# detector328p-pu.net
KiCad netlist of a schematic drawn in EAGLE
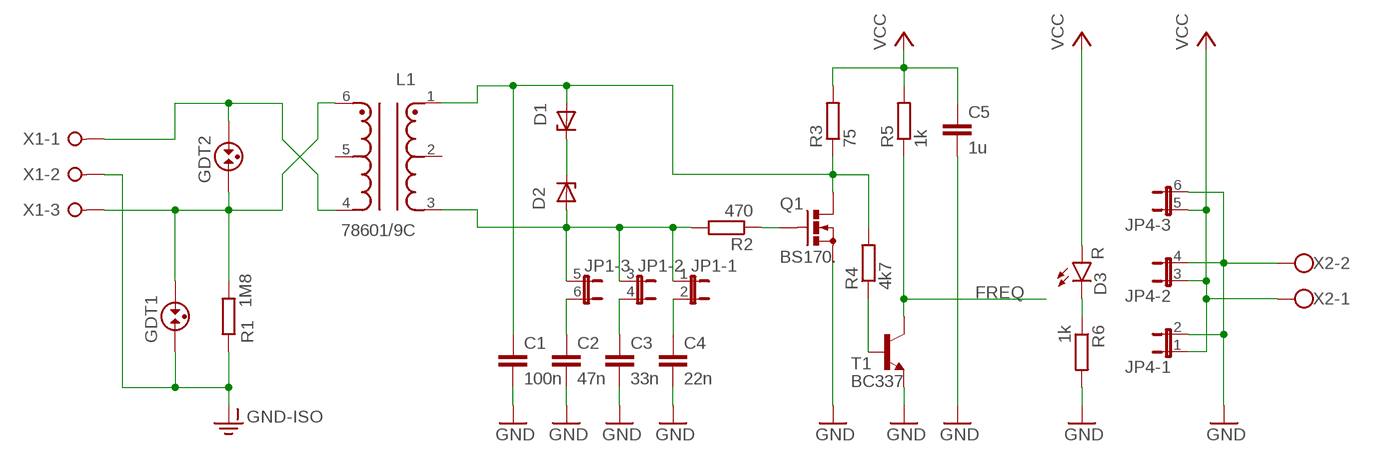
[diagram p0: schematic, sheet 1]
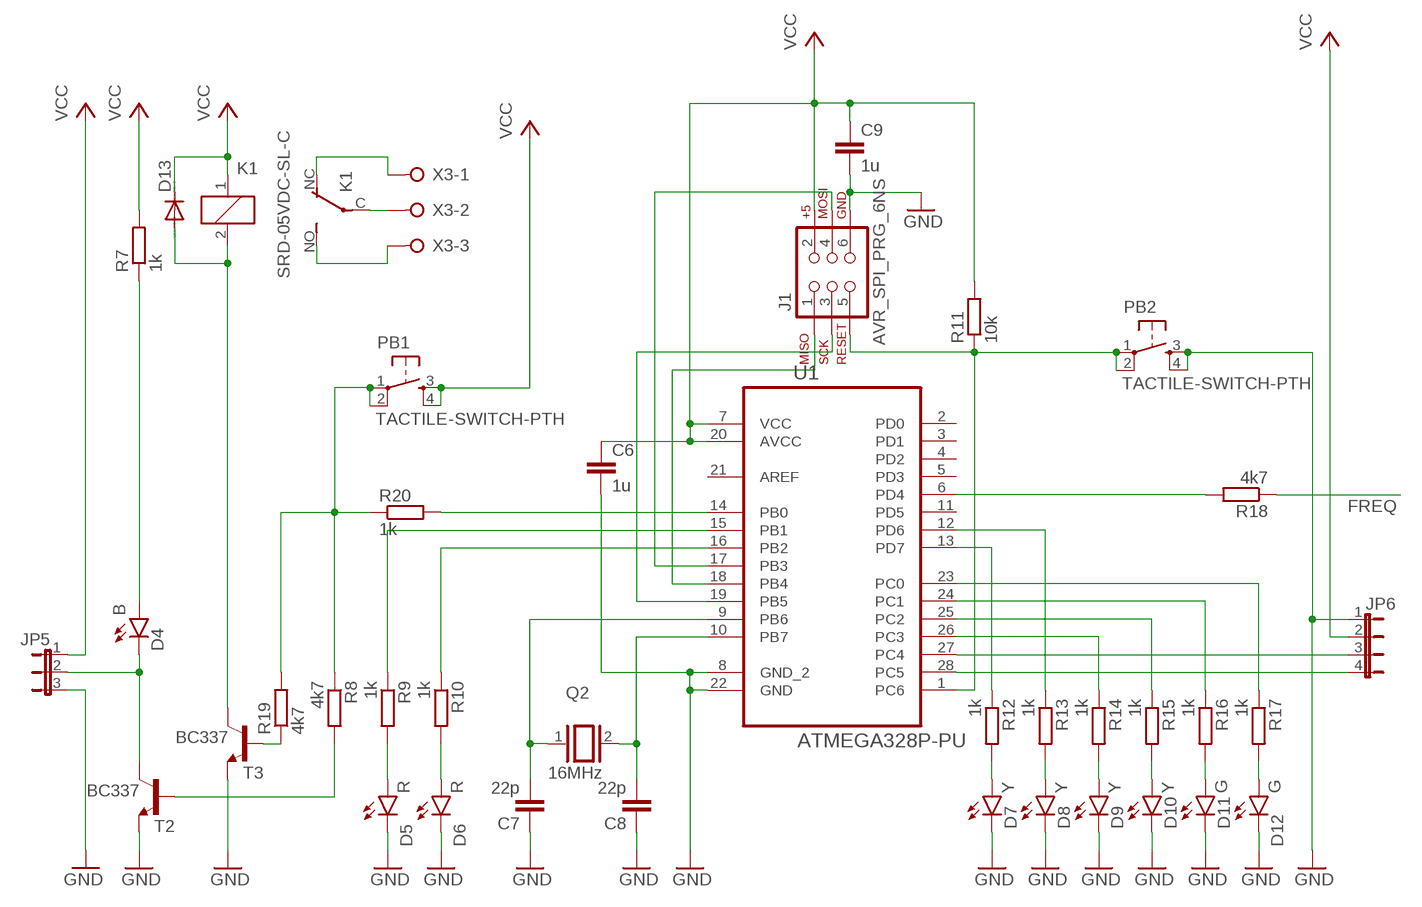
[diagram p1: schematic, sheet 2]

(export (version "E")
  (design (tool "Eeschema 10.0.6"))
  (components
    (comp (ref "C6")
      (value "1u")
      (footprint "eagle-import:C025-030X050")
      (libsource (lib "eagle-import") (part "C-EU025-030X050"))
    )
    (comp (ref "C7")
      (value "22p")
      (footprint "eagle-import:C025-025X050")
      (libsource (lib "eagle-import") (part "resistor_C-EU025-025X050"))
    )
    (comp (ref "C8")
      (value "22p")
      (footprint "eagle-import:C025-025X050")
      (libsource (lib "eagle-import") (part "resistor_C-EU025-025X050"))
    )
    (comp (ref "C9")
      (value "1u")
      (footprint "eagle-import:C025-030X050")
      (libsource (lib "eagle-import") (part "C-EU025-030X050"))
    )
    (comp (ref "D4")
      (value "B")
      (footprint "eagle-import:LED3MM")
      (libsource (lib "eagle-import") (part "LED3MM"))
    )
    (comp (ref "D5")
      (value "R")
      (footprint "eagle-import:LED3MM")
      (libsource (lib "eagle-import") (part "LED3MM"))
    )
    (comp (ref "D6")
      (value "R")
      (footprint "eagle-import:LED3MM")
      (libsource (lib "eagle-import") (part "LED3MM"))
    )
    (comp (ref "D7")
      (value "Y")
      (footprint "eagle-import:LED3MM")
      (libsource (lib "eagle-import") (part "LED3MM"))
    )
    (comp (ref "D8")
      (value "Y")
      (footprint "eagle-import:LED3MM")
      (libsource (lib "eagle-import") (part "LED3MM"))
    )
    (comp (ref "D9")
      (value "Y")
      (footprint "eagle-import:LED3MM")
      (libsource (lib "eagle-import") (part "LED3MM"))
    )
    (comp (ref "D10")
      (value "Y")
      (footprint "eagle-import:LED3MM")
      (libsource (lib "eagle-import") (part "LED3MM"))
    )
    (comp (ref "D11")
      (value "G")
      (footprint "eagle-import:LED3MM")
      (libsource (lib "eagle-import") (part "LED3MM"))
    )
    (comp (ref "D12")
      (value "G")
      (footprint "eagle-import:LED3MM")
      (libsource (lib "eagle-import") (part "LED3MM"))
    )
    (comp (ref "D13")
      (value "DIODE-D-5")
      (footprint "eagle-import:D-5")
      (libsource (lib "eagle-import") (part "DIODE-D-5"))
    )
    (comp (ref "J1")
      (value "AVR_SPI_PRG_6NS")
      (footprint "eagle-import:2X3-NS")
      (libsource (lib "eagle-import") (part "AVR_SPI_PRG_6NS"))
    )
    (comp (ref "JP5")
      (value "JP2E")
      (footprint "eagle-import:JP2")
      (libsource (lib "eagle-import") (part "JP2E"))
    )
    (comp (ref "JP6")
      (value "JP4E")
      (footprint "eagle-import:JP4")
      (libsource (lib "eagle-import") (part "JP4E"))
    )
    (comp (ref "K1")
      (value "SRD-05VDC-SL-C")
      (footprint "eagle-import:JS-M")
      (libsource (lib "eagle-import") (part "SRD--SL-C05VDC"))
    )
    (comp (ref "PB1")
      (value "TACTILE-SWITCH-PTH")
      (footprint "eagle-import:TAC-SWITCH-PTH")
      (libsource (lib "eagle-import") (part "TACTILE-SWITCH-PTH"))
    )
    (comp (ref "PB2")
      (value "TACTILE-SWITCH-PTH")
      (footprint "eagle-import:TAC-SWITCH-PTH")
      (libsource (lib "eagle-import") (part "TACTILE-SWITCH-PTH"))
    )
    (comp (ref "Q2")
      (value "16MHz")
      (footprint "eagle-import:QS")
      (libsource (lib "eagle-import") (part "XTAL/S"))
    )
    (comp (ref "R7")
      (value "1k")
      (footprint "eagle-import:0204_5")
      (libsource (lib "eagle-import") (part "R-EU_0204/5"))
    )
    (comp (ref "R8")
      (value "4k7")
      (footprint "eagle-import:0204_5")
      (libsource (lib "eagle-import") (part "R-EU_0204/5"))
    )
    (comp (ref "R9")
      (value "1k")
      (footprint "eagle-import:0204_5")
      (libsource (lib "eagle-import") (part "R-EU_0204/5"))
    )
    (comp (ref "R10")
      (value "1k")
      (footprint "eagle-import:0204_5")
      (libsource (lib "eagle-import") (part "R-EU_0204/5"))
    )
    (comp (ref "R11")
      (value "10k")
      (footprint "eagle-import:0204_5")
      (libsource (lib "eagle-import") (part "R-EU_0204/5"))
    )
    (comp (ref "R12")
      (value "1k")
      (footprint "eagle-import:0204_5")
      (libsource (lib "eagle-import") (part "R-EU_0204/5"))
    )
    (comp (ref "R13")
      (value "1k")
      (footprint "eagle-import:0204_5")
      (libsource (lib "eagle-import") (part "R-EU_0204/5"))
    )
    (comp (ref "R14")
      (value "1k")
      (footprint "eagle-import:0204_5")
      (libsource (lib "eagle-import") (part "R-EU_0204/5"))
    )
    (comp (ref "R15")
      (value "1k")
      (footprint "eagle-import:0204_5")
      (libsource (lib "eagle-import") (part "R-EU_0204/5"))
    )
    (comp (ref "R16")
      (value "1k")
      (footprint "eagle-import:0204_5")
      (libsource (lib "eagle-import") (part "R-EU_0204/5"))
    )
    (comp (ref "R17")
      (value "1k")
      (footprint "eagle-import:0204_5")
      (libsource (lib "eagle-import") (part "R-EU_0204/5"))
    )
    (comp (ref "R18")
      (value "4k7")
      (footprint "eagle-import:0204_5")
      (libsource (lib "eagle-import") (part "R-EU_0204/5"))
    )
    (comp (ref "R19")
      (value "4k7")
      (footprint "eagle-import:0204_5")
      (libsource (lib "eagle-import") (part "R-EU_0204/5"))
    )
    (comp (ref "R20")
      (value "1k")
      (footprint "eagle-import:0204_5")
      (libsource (lib "eagle-import") (part "R-EU_0204/5"))
    )
    (comp (ref "T2")
      (value "BC337")
      (footprint "eagle-import:TO92-CBE")
      (libsource (lib "eagle-import") (part "-NPN-TO92-CBEBC337"))
    )
    (comp (ref "T3")
      (value "BC337")
      (footprint "eagle-import:TO92-CBE")
      (libsource (lib "eagle-import") (part "-NPN-TO92-CBEBC337"))
    )
    (comp (ref "U1")
      (value "ATMEGA328P-PU")
      (footprint "eagle-import:DIP254P762X457-28")
      (libsource (lib "eagle-import") (part "ATMEGA328P-PU"))
    )
    (comp (ref "X3")
      (value "W237-03P")
      (footprint "eagle-import:W237-133")
      (libsource (lib "eagle-import") (part "W237-03P"))
    )
    (comp (ref "C1")
      (value "100n")
      (footprint "eagle-import:C025-025X050")
      (libsource (lib "eagle-import") (part "resistor_C-EU025-025X050"))
    )
    (comp (ref "C2")
      (value "47n")
      (footprint "eagle-import:C025-025X050")
      (libsource (lib "eagle-import") (part "resistor_C-EU025-025X050"))
    )
    (comp (ref "C3")
      (value "33n")
      (footprint "eagle-import:C025-025X050")
      (libsource (lib "eagle-import") (part "resistor_C-EU025-025X050"))
    )
    (comp (ref "C4")
      (value "22n")
      (footprint "eagle-import:C025-025X050")
      (libsource (lib "eagle-import") (part "resistor_C-EU025-025X050"))
    )
    (comp (ref "C5")
      (value "1u")
      (footprint "eagle-import:C025-030X050")
      (libsource (lib "eagle-import") (part "C-EU025-030X050"))
    )
    (comp (ref "D1")
      (value "24V")
      (footprint "eagle-import:ZDIO-5")
      (libsource (lib "eagle-import") (part "ZENER-DIODEZD-5"))
    )
    (comp (ref "D2")
      (value "24V")
      (footprint "eagle-import:ZDIO-5")
      (libsource (lib "eagle-import") (part "ZENER-DIODEZD-5"))
    )
    (comp (ref "D3")
      (value "R")
      (footprint "eagle-import:LED3MM")
      (libsource (lib "eagle-import") (part "LED3MM"))
    )
    (comp (ref "GDT1")
      (value "GDT-CG5350L")
      (footprint "eagle-import:CG5350L")
      (libsource (lib "eagle-import") (part "GDT-CG5350L"))
    )
    (comp (ref "GDT2")
      (value "GDT-CG5350L")
      (footprint "eagle-import:CG5350L")
      (libsource (lib "eagle-import") (part "GDT-CG5350L"))
    )
    (comp (ref "JP1")
      (value "JP3QE")
      (footprint "eagle-import:JP3Q")
      (libsource (lib "eagle-import") (part "JP3QE"))
    )
    (comp (ref "JP4")
      (value "JP3QE")
      (footprint "eagle-import:JP3Q")
      (libsource (lib "eagle-import") (part "JP3QE"))
    )
    (comp (ref "L1")
      (value "78601/9C")
      (footprint "eagle-import:78601_9C")
      (libsource (lib "eagle-import") (part "78601/9C"))
    )
    (comp (ref "Q1")
      (value "BS170.")
      (footprint "eagle-import:TO92-DGS")
      (libsource (lib "eagle-import") (part "BS170."))
    )
    (comp (ref "R1")
      (value "1M8")
      (footprint "eagle-import:0204_5")
      (libsource (lib "eagle-import") (part "R-EU_0204/5"))
    )
    (comp (ref "R2")
      (value "470")
      (footprint "eagle-import:0204_5")
      (libsource (lib "eagle-import") (part "R-EU_0204/5"))
    )
    (comp (ref "R3")
      (value "75")
      (footprint "eagle-import:0204_7")
      (libsource (lib "eagle-import") (part "R-EU_0204/7"))
    )
    (comp (ref "R4")
      (value "4k7")
      (footprint "eagle-import:0204_5")
      (libsource (lib "eagle-import") (part "R-EU_0204/5"))
    )
    (comp (ref "R5")
      (value "1k")
      (footprint "eagle-import:0204_5")
      (libsource (lib "eagle-import") (part "R-EU_0204/5"))
    )
    (comp (ref "R6")
      (value "1k")
      (footprint "eagle-import:0204_5")
      (libsource (lib "eagle-import") (part "R-EU_0204/5"))
    )
    (comp (ref "T1")
      (value "BC337")
      (footprint "eagle-import:TO92-CBE")
      (libsource (lib "eagle-import") (part "-NPN-TO92-CBEBC337"))
    )
    (comp (ref "X1")
      (value "W237-03P")
      (footprint "eagle-import:W237-133")
      (libsource (lib "eagle-import") (part "W237-03P"))
    )
    (comp (ref "X2")
      (value "W237-102")
      (footprint "eagle-import:W237-102")
      (fields (field (name "MPN") "237-102"))
      (libsource (lib "eagle-import") (part "W237-102"))
    )
  )
  (nets
    (net (code "1") (name "FREQ") (class "Default")
      (node (ref "R18") (pin "1") (pinfunction "1_1") (pintype "passive"))
      (node (ref "R5") (pin "1") (pinfunction "1_1") (pintype "passive"))
      (node (ref "T1") (pin "C") (pinfunction "C_C") (pintype "passive"))
    )
    (net (code "2") (name "GND") (class "Default")
      (node (ref "C1") (pin "2") (pinfunction "2_2") (pintype "passive"))
      (node (ref "C2") (pin "2") (pinfunction "2_2") (pintype "passive"))
      (node (ref "C3") (pin "2") (pinfunction "2_2") (pintype "passive"))
      (node (ref "C4") (pin "2") (pinfunction "2_2") (pintype "passive"))
      (node (ref "C5") (pin "2") (pinfunction "2_2") (pintype "passive"))
      (node (ref "C6") (pin "2") (pinfunction "2_2") (pintype "passive"))
      (node (ref "C7") (pin "1") (pinfunction "1_1") (pintype "passive"))
      (node (ref "C8") (pin "1") (pinfunction "1_1") (pintype "passive"))
      (node (ref "C9") (pin "2") (pinfunction "2_2") (pintype "passive"))
      (node (ref "D10") (pin "K") (pinfunction "C_K") (pintype "passive"))
      (node (ref "D11") (pin "K") (pinfunction "C_K") (pintype "passive"))
      (node (ref "D12") (pin "K") (pinfunction "C_K") (pintype "passive"))
      (node (ref "D5") (pin "K") (pinfunction "C_K") (pintype "passive"))
      (node (ref "D6") (pin "K") (pinfunction "C_K") (pintype "passive"))
      (node (ref "D7") (pin "K") (pinfunction "C_K") (pintype "passive"))
      (node (ref "D8") (pin "K") (pinfunction "C_K") (pintype "passive"))
      (node (ref "D9") (pin "K") (pinfunction "C_K") (pintype "passive"))
      (node (ref "J1") (pin "6") (pinfunction "6_6") (pintype "passive"))
      (node (ref "JP4") (pin "2") (pinfunction "2_2") (pintype "passive"))
      (node (ref "JP4") (pin "4") (pinfunction "2_4") (pintype "passive"))
      (node (ref "JP4") (pin "6") (pinfunction "2_6") (pintype "passive"))
      (node (ref "JP5") (pin "3") (pinfunction "3_3") (pintype "passive"))
      (node (ref "JP6") (pin "1") (pinfunction "1_1") (pintype "passive"))
      (node (ref "PB2") (pin "3") (pinfunction "3_3") (pintype "passive"))
      (node (ref "PB2") (pin "4") (pinfunction "4_4") (pintype "passive"))
      (node (ref "Q1") (pin "S") (pinfunction "S_S") (pintype "passive"))
      (node (ref "R6") (pin "2") (pinfunction "2_2") (pintype "passive"))
      (node (ref "T1") (pin "E") (pinfunction "E_E") (pintype "passive"))
      (node (ref "T2") (pin "E") (pinfunction "E_E") (pintype "passive"))
      (node (ref "T3") (pin "E") (pinfunction "E_E") (pintype "passive"))
      (node (ref "U1") (pin "22") (pinfunction "GND_22") (pintype "passive"))
      (node (ref "U1") (pin "8") (pinfunction "GND_2_8") (pintype "passive"))
      (node (ref "X2") (pin "2") (pinfunction "KL_2") (pintype "passive"))
    )
    (net (code "3") (name "GND-ISO") (class "Default")
      (node (ref "GDT1") (pin "1") (pinfunction "1_1") (pintype "passive"))
      (node (ref "R1") (pin "1") (pinfunction "1_1") (pintype "passive"))
      (node (ref "X1") (pin "2") (pinfunction "KL_2") (pintype "passive"))
    )
    (net (code "4") (name "Net-(C1-Pad1)") (class "Default")
      (node (ref "C1") (pin "1") (pinfunction "1_1") (pintype "passive"))
      (node (ref "D1") (pin "A") (pinfunction "A_A") (pintype "passive"))
      (node (ref "L1") (pin "1") (pinfunction "1_1") (pintype "passive"))
      (node (ref "Q1") (pin "D") (pinfunction "D_D") (pintype "passive"))
      (node (ref "R3") (pin "1") (pinfunction "1_1") (pintype "passive"))
      (node (ref "R4") (pin "2") (pinfunction "2_2") (pintype "passive"))
    )
    (net (code "5") (name "Net-(C4-Pad1)") (class "Default")
      (node (ref "C4") (pin "1") (pinfunction "1_1") (pintype "passive"))
      (node (ref "JP1") (pin "2") (pinfunction "2_2") (pintype "passive"))
    )
    (net (code "6") (name "Net-(D1-PadC)") (class "Default")
      (node (ref "D1") (pin "C") (pinfunction "C_C") (pintype "passive"))
      (node (ref "D2") (pin "C") (pinfunction "C_C") (pintype "passive"))
    )
    (net (code "7") (name "Net-(D3-C)") (class "Default")
      (node (ref "D3") (pin "K") (pinfunction "C_K") (pintype "passive"))
      (node (ref "R6") (pin "1") (pinfunction "1_1") (pintype "passive"))
    )
    (net (code "8") (name "Net-(D4-C)") (class "Default")
      (node (ref "D4") (pin "K") (pinfunction "C_K") (pintype "passive"))
      (node (ref "JP5") (pin "2") (pinfunction "2_2") (pintype "passive"))
      (node (ref "T2") (pin "C") (pinfunction "C_C") (pintype "passive"))
    )
    (net (code "9") (name "Net-(D4-PadA)") (class "Default")
      (node (ref "D4") (pin "A") (pinfunction "A_A") (pintype "passive"))
      (node (ref "R7") (pin "1") (pinfunction "1_1") (pintype "passive"))
    )
    (net (code "10") (name "Net-(D5-PadA)") (class "Default")
      (node (ref "D5") (pin "A") (pinfunction "A_A") (pintype "passive"))
      (node (ref "R9") (pin "2") (pinfunction "2_2") (pintype "passive"))
    )
    (net (code "11") (name "Net-(D6-PadA)") (class "Default")
      (node (ref "D6") (pin "A") (pinfunction "A_A") (pintype "passive"))
      (node (ref "R10") (pin "2") (pinfunction "2_2") (pintype "passive"))
    )
    (net (code "12") (name "Net-(D7-PadA)") (class "Default")
      (node (ref "D7") (pin "A") (pinfunction "A_A") (pintype "passive"))
      (node (ref "R12") (pin "2") (pinfunction "2_2") (pintype "passive"))
    )
    (net (code "13") (name "Net-(D8-PadA)") (class "Default")
      (node (ref "D8") (pin "A") (pinfunction "A_A") (pintype "passive"))
      (node (ref "R13") (pin "2") (pinfunction "2_2") (pintype "passive"))
    )
    (net (code "14") (name "Net-(D9-PadA)") (class "Default")
      (node (ref "D9") (pin "A") (pinfunction "A_A") (pintype "passive"))
      (node (ref "R14") (pin "2") (pinfunction "2_2") (pintype "passive"))
    )
    (net (code "15") (name "Net-(D10-PadA)") (class "Default")
      (node (ref "D10") (pin "A") (pinfunction "A_A") (pintype "passive"))
      (node (ref "R15") (pin "2") (pinfunction "2_2") (pintype "passive"))
    )
    (net (code "16") (name "Net-(D11-PadA)") (class "Default")
      (node (ref "D11") (pin "A") (pinfunction "A_A") (pintype "passive"))
      (node (ref "R16") (pin "2") (pinfunction "2_2") (pintype "passive"))
    )
    (net (code "17") (name "Net-(D12-PadA)") (class "Default")
      (node (ref "D12") (pin "A") (pinfunction "A_A") (pintype "passive"))
      (node (ref "R17") (pin "2") (pinfunction "2_2") (pintype "passive"))
    )
    (net (code "18") (name "Net-(D13-PadA)") (class "Default")
      (node (ref "D13") (pin "A") (pinfunction "A_A") (pintype "passive"))
      (node (ref "K1") (pin "2") (pinfunction "2_2") (pintype "passive"))
      (node (ref "T3") (pin "C") (pinfunction "C_C") (pintype "passive"))
    )
    (net (code "19") (name "Net-(JP1B-1)") (class "Default")
      (node (ref "D2") (pin "A") (pinfunction "A_A") (pintype "passive"))
      (node (ref "JP1") (pin "1") (pinfunction "1_1") (pintype "passive"))
      (node (ref "JP1") (pin "3") (pinfunction "1_3") (pintype "passive"))
      (node (ref "JP1") (pin "5") (pinfunction "1_5") (pintype "passive"))
      (node (ref "L1") (pin "3") (pinfunction "3_3") (pintype "passive"))
      (node (ref "R2") (pin "2") (pinfunction "2_2") (pintype "passive"))
    )
    (net (code "20") (name "Net-(JP1B-2)") (class "Default")
      (node (ref "C3") (pin "1") (pinfunction "1_1") (pintype "passive"))
      (node (ref "JP1") (pin "4") (pinfunction "2_4") (pintype "passive"))
    )
    (net (code "21") (name "Net-(JP1C-2)") (class "Default")
      (node (ref "C2") (pin "1") (pinfunction "1_1") (pintype "passive"))
      (node (ref "JP1") (pin "6") (pinfunction "2_6") (pintype "passive"))
    )
    (net (code "22") (name "Net-(K1B-O)") (class "Default")
      (node (ref "K1") (pin "NC") (pinfunction "O_NC") (pintype "passive"))
      (node (ref "X3") (pin "1") (pinfunction "KL_1") (pintype "passive"))
    )
    (net (code "23") (name "Net-(K1B-P)") (class "Default")
      (node (ref "K1") (pin "C") (pinfunction "P_C") (pintype "passive"))
      (node (ref "X3") (pin "2") (pinfunction "KL_2") (pintype "passive"))
    )
    (net (code "24") (name "Net-(K1B-S)") (class "Default")
      (node (ref "K1") (pin "NO") (pinfunction "S_NO") (pintype "passive"))
      (node (ref "X3") (pin "3") (pinfunction "KL_3") (pintype "passive"))
    )
    (net (code "25") (name "Net-(PB1-Pad1)") (class "Default")
      (node (ref "PB1") (pin "1") (pinfunction "1_1") (pintype "passive"))
      (node (ref "PB1") (pin "2") (pinfunction "2_2") (pintype "passive"))
      (node (ref "R19") (pin "2") (pinfunction "2_2") (pintype "passive"))
      (node (ref "R20") (pin "1") (pinfunction "1_1") (pintype "passive"))
      (node (ref "R8") (pin "1") (pinfunction "1_1") (pintype "passive"))
    )
    (net (code "26") (name "Net-(Q1-PadG)") (class "Default")
      (node (ref "Q1") (pin "G") (pinfunction "G_G") (pintype "passive"))
      (node (ref "R2") (pin "1") (pinfunction "1_1") (pintype "passive"))
    )
    (net (code "27") (name "Net-(R4-Pad1)") (class "Default")
      (node (ref "R4") (pin "1") (pinfunction "1_1") (pintype "passive"))
      (node (ref "T1") (pin "B") (pinfunction "B_B") (pintype "passive"))
    )
    (net (code "28") (name "Net-(R8-Pad2)") (class "Default")
      (node (ref "R8") (pin "2") (pinfunction "2_2") (pintype "passive"))
      (node (ref "T2") (pin "B") (pinfunction "B_B") (pintype "passive"))
    )
    (net (code "29") (name "Net-(R19-Pad1)") (class "Default")
      (node (ref "R19") (pin "1") (pinfunction "1_1") (pintype "passive"))
      (node (ref "T3") (pin "B") (pinfunction "B_B") (pintype "passive"))
    )
    (net (code "30") (name "Net-(U1-PB0)") (class "Default")
      (node (ref "R20") (pin "2") (pinfunction "2_2") (pintype "passive"))
      (node (ref "U1") (pin "14") (pinfunction "PB0_14") (pintype "bidirectional"))
    )
    (net (code "31") (name "Net-(U1-PB1)") (class "Default")
      (node (ref "R9") (pin "1") (pinfunction "1_1") (pintype "passive"))
      (node (ref "U1") (pin "15") (pinfunction "PB1_15") (pintype "bidirectional"))
    )
    (net (code "32") (name "Net-(U1-PB2)") (class "Default")
      (node (ref "R10") (pin "1") (pinfunction "1_1") (pintype "passive"))
      (node (ref "U1") (pin "16") (pinfunction "PB2_16") (pintype "bidirectional"))
    )
    (net (code "33") (name "Net-(U1-PB3)") (class "Default")
      (node (ref "J1") (pin "4") (pinfunction "4_4") (pintype "passive"))
      (node (ref "U1") (pin "17") (pinfunction "PB3_17") (pintype "bidirectional"))
    )
    (net (code "34") (name "Net-(U1-PB4)") (class "Default")
      (node (ref "J1") (pin "1") (pinfunction "1_1") (pintype "passive"))
      (node (ref "U1") (pin "18") (pinfunction "PB4_18") (pintype "bidirectional"))
    )
    (net (code "35") (name "Net-(U1-PB5)") (class "Default")
      (node (ref "J1") (pin "3") (pinfunction "3_3") (pintype "passive"))
      (node (ref "U1") (pin "19") (pinfunction "PB5_19") (pintype "bidirectional"))
    )
    (net (code "36") (name "Net-(U1-PB6)") (class "Default")
      (node (ref "C7") (pin "2") (pinfunction "2_2") (pintype "passive"))
      (node (ref "Q2") (pin "1") (pinfunction "1_1") (pintype "passive"))
      (node (ref "U1") (pin "9") (pinfunction "PB6_9") (pintype "bidirectional"))
    )
    (net (code "37") (name "Net-(U1-PB7)") (class "Default")
      (node (ref "C8") (pin "2") (pinfunction "2_2") (pintype "passive"))
      (node (ref "Q2") (pin "2") (pinfunction "2_2") (pintype "passive"))
      (node (ref "U1") (pin "10") (pinfunction "PB7_10") (pintype "bidirectional"))
    )
    (net (code "38") (name "Net-(U1-PC0)") (class "Default")
      (node (ref "R17") (pin "1") (pinfunction "1_1") (pintype "passive"))
      (node (ref "U1") (pin "23") (pinfunction "PC0_23") (pintype "bidirectional"))
    )
    (net (code "39") (name "Net-(U1-PC1)") (class "Default")
      (node (ref "R16") (pin "1") (pinfunction "1_1") (pintype "passive"))
      (node (ref "U1") (pin "24") (pinfunction "PC1_24") (pintype "bidirectional"))
    )
    (net (code "40") (name "Net-(U1-PC2)") (class "Default")
      (node (ref "R15") (pin "1") (pinfunction "1_1") (pintype "passive"))
      (node (ref "U1") (pin "25") (pinfunction "PC2_25") (pintype "bidirectional"))
    )
    (net (code "41") (name "Net-(U1-PC3)") (class "Default")
      (node (ref "R14") (pin "1") (pinfunction "1_1") (pintype "passive"))
      (node (ref "U1") (pin "26") (pinfunction "PC3_26") (pintype "bidirectional"))
    )
    (net (code "42") (name "Net-(U1-PC4)") (class "Default")
      (node (ref "JP6") (pin "3") (pinfunction "3_3") (pintype "passive"))
      (node (ref "U1") (pin "27") (pinfunction "PC4_27") (pintype "bidirectional"))
    )
    (net (code "43") (name "Net-(U1-PC5)") (class "Default")
      (node (ref "JP6") (pin "4") (pinfunction "4_4") (pintype "passive"))
      (node (ref "U1") (pin "28") (pinfunction "PC5_28") (pintype "bidirectional"))
    )
    (net (code "44") (name "Net-(U1-PC6)") (class "Default")
      (node (ref "J1") (pin "5") (pinfunction "5_5") (pintype "passive"))
      (node (ref "PB2") (pin "1") (pinfunction "1_1") (pintype "passive"))
      (node (ref "PB2") (pin "2") (pinfunction "2_2") (pintype "passive"))
      (node (ref "R11") (pin "1") (pinfunction "1_1") (pintype "passive"))
      (node (ref "U1") (pin "1") (pinfunction "PC6_1") (pintype "bidirectional"))
    )
    (net (code "45") (name "Net-(U1-PD4)") (class "Default")
      (node (ref "R18") (pin "2") (pinfunction "2_2") (pintype "passive"))
      (node (ref "U1") (pin "6") (pinfunction "PD4_6") (pintype "bidirectional"))
    )
    (net (code "46") (name "Net-(U1-PD6)") (class "Default")
      (node (ref "R13") (pin "1") (pinfunction "1_1") (pintype "passive"))
      (node (ref "U1") (pin "12") (pinfunction "PD6_12") (pintype "bidirectional"))
    )
    (net (code "47") (name "Net-(U1-PD7)") (class "Default")
      (node (ref "R12") (pin "1") (pinfunction "1_1") (pintype "passive"))
      (node (ref "U1") (pin "13") (pinfunction "PD7_13") (pintype "bidirectional"))
    )
    (net (code "48") (name "Net-(X1A-KL)") (class "Default")
      (node (ref "GDT2") (pin "2") (pinfunction "2_2") (pintype "passive"))
      (node (ref "L1") (pin "4") (pinfunction "4_4") (pintype "passive"))
      (node (ref "X1") (pin "1") (pinfunction "KL_1") (pintype "passive"))
    )
    (net (code "49") (name "Net-(X1C-KL)") (class "Default")
      (node (ref "GDT1") (pin "2") (pinfunction "2_2") (pintype "passive"))
      (node (ref "GDT2") (pin "1") (pinfunction "1_1") (pintype "passive"))
      (node (ref "L1") (pin "6") (pinfunction "6_6") (pintype "passive"))
      (node (ref "R1") (pin "2") (pinfunction "2_2") (pintype "passive"))
      (node (ref "X1") (pin "3") (pinfunction "KL_3") (pintype "passive"))
    )
    (net (code "50") (name "VCC") (class "Default")
      (node (ref "C5") (pin "1") (pinfunction "1_1") (pintype "passive"))
      (node (ref "C6") (pin "1") (pinfunction "1_1") (pintype "passive"))
      (node (ref "C9") (pin "1") (pinfunction "1_1") (pintype "passive"))
      (node (ref "D13") (pin "C") (pinfunction "C_C") (pintype "passive"))
      (node (ref "D3") (pin "A") (pinfunction "A_A") (pintype "passive"))
      (node (ref "J1") (pin "2") (pinfunction "2_2") (pintype "passive"))
      (node (ref "JP4") (pin "1") (pinfunction "1_1") (pintype "passive"))
      (node (ref "JP4") (pin "3") (pinfunction "1_3") (pintype "passive"))
      (node (ref "JP4") (pin "5") (pinfunction "1_5") (pintype "passive"))
      (node (ref "JP5") (pin "1") (pinfunction "1_1") (pintype "passive"))
      (node (ref "JP6") (pin "2") (pinfunction "2_2") (pintype "passive"))
      (node (ref "K1") (pin "1") (pinfunction "1_1") (pintype "passive"))
      (node (ref "PB1") (pin "3") (pinfunction "3_3") (pintype "passive"))
      (node (ref "PB1") (pin "4") (pinfunction "4_4") (pintype "passive"))
      (node (ref "R11") (pin "2") (pinfunction "2_2") (pintype "passive"))
      (node (ref "R3") (pin "2") (pinfunction "2_2") (pintype "passive"))
      (node (ref "R5") (pin "2") (pinfunction "2_2") (pintype "passive"))
      (node (ref "R7") (pin "2") (pinfunction "2_2") (pintype "passive"))
      (node (ref "U1") (pin "20") (pinfunction "AVCC_20") (pintype "power_in"))
      (node (ref "U1") (pin "7") (pinfunction "VCC_7") (pintype "power_in"))
      (node (ref "X2") (pin "1") (pinfunction "KL_1") (pintype "passive"))
    )
    (net (code "51") (name "unconnected-(L1-Pad2)") (class "Default")
      (node (ref "L1") (pin "2") (pinfunction "2_2") (pintype "passive"))
    )
    (net (code "52") (name "unconnected-(L1-Pad5)") (class "Default")
      (node (ref "L1") (pin "5") (pinfunction "5_5") (pintype "passive"))
    )
    (net (code "53") (name "unconnected-(U1-AREF-Pad21)") (class "Default")
      (node (ref "U1") (pin "21") (pinfunction "AREF_21") (pintype "input"))
    )
    (net (code "54") (name "unconnected-(U1-PD0-Pad2)") (class "Default")
      (node (ref "U1") (pin "2") (pinfunction "PD0_2") (pintype "bidirectional"))
    )
    (net (code "55") (name "unconnected-(U1-PD1-Pad3)") (class "Default")
      (node (ref "U1") (pin "3") (pinfunction "PD1_3") (pintype "bidirectional"))
    )
    (net (code "56") (name "unconnected-(U1-PD2-Pad4)") (class "Default")
      (node (ref "U1") (pin "4") (pinfunction "PD2_4") (pintype "bidirectional"))
    )
    (net (code "57") (name "unconnected-(U1-PD3-Pad5)") (class "Default")
      (node (ref "U1") (pin "5") (pinfunction "PD3_5") (pintype "bidirectional"))
    )
    (net (code "58") (name "unconnected-(U1-PD5-Pad11)") (class "Default")
      (node (ref "U1") (pin "11") (pinfunction "PD5_11") (pintype "bidirectional"))
    )
  )
)
